# TMR2017.net
KiCad netlist of a schematic drawn in EAGLE
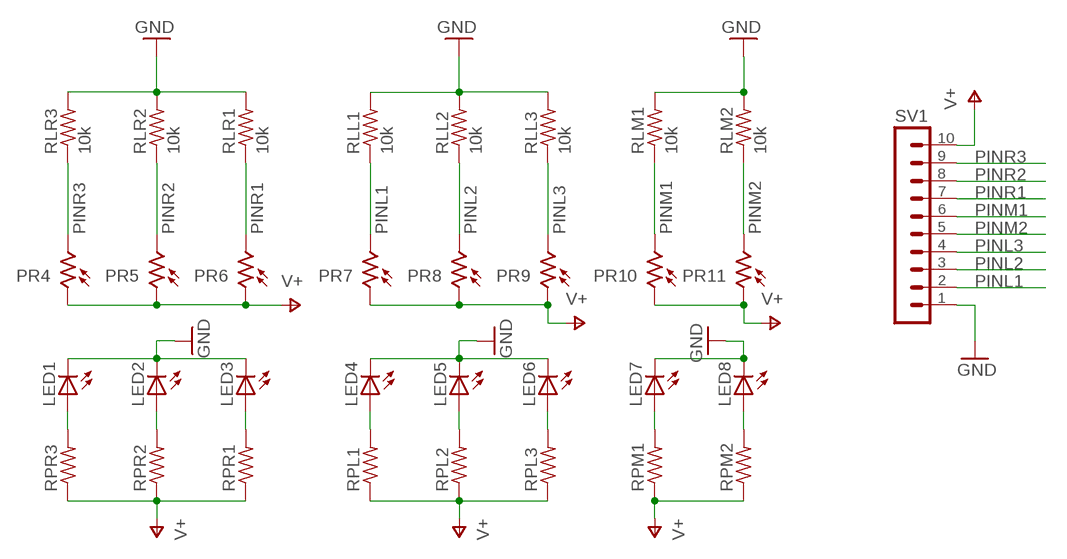
[diagram p0: schematic, sheet 1]

(export (version "E")
  (design (tool "Eeschema 10.0.6"))
  (components
    (comp (ref "LED1")
      (value "TLLR4400")
      (footprint "eagle-import:LED3MM")
      (fields (field (name "MF") "VISHAY SEMICONDUCTOR"))
      (libsource (lib "eagle-import") (part "TLLR4400"))
    )
    (comp (ref "LED2")
      (value "TLLR4400")
      (footprint "eagle-import:LED3MM")
      (fields (field (name "MF") "VISHAY SEMICONDUCTOR"))
      (libsource (lib "eagle-import") (part "TLLR4400"))
    )
    (comp (ref "LED3")
      (value "TLLR4400")
      (footprint "eagle-import:LED3MM")
      (fields (field (name "MF") "VISHAY SEMICONDUCTOR"))
      (libsource (lib "eagle-import") (part "TLLR4400"))
    )
    (comp (ref "LED4")
      (value "TLLR4400")
      (footprint "eagle-import:LED3MM")
      (fields (field (name "MF") "VISHAY SEMICONDUCTOR"))
      (libsource (lib "eagle-import") (part "TLLR4400"))
    )
    (comp (ref "LED5")
      (value "TLLR4400")
      (footprint "eagle-import:LED3MM")
      (fields (field (name "MF") "VISHAY SEMICONDUCTOR"))
      (libsource (lib "eagle-import") (part "TLLR4400"))
    )
    (comp (ref "LED6")
      (value "TLLR4400")
      (footprint "eagle-import:LED3MM")
      (fields (field (name "MF") "VISHAY SEMICONDUCTOR"))
      (libsource (lib "eagle-import") (part "TLLR4400"))
    )
    (comp (ref "LED7")
      (value "TLLR4400")
      (footprint "eagle-import:LED3MM")
      (fields (field (name "MF") "VISHAY SEMICONDUCTOR"))
      (libsource (lib "eagle-import") (part "TLLR4400"))
    )
    (comp (ref "LED8")
      (value "TLLR4400")
      (footprint "eagle-import:LED3MM")
      (fields (field (name "MF") "VISHAY SEMICONDUCTOR"))
      (libsource (lib "eagle-import") (part "TLLR4400"))
    )
    (comp (ref "PR4")
      (value "VT80N1")
      (footprint "eagle-import:VT800")
      (libsource (lib "eagle-import") (part "VT80N1"))
    )
    (comp (ref "PR5")
      (value "VT80N1")
      (footprint "eagle-import:VT800")
      (libsource (lib "eagle-import") (part "VT80N1"))
    )
    (comp (ref "PR6")
      (value "VT80N1")
      (footprint "eagle-import:VT800")
      (libsource (lib "eagle-import") (part "VT80N1"))
    )
    (comp (ref "PR7")
      (value "VT80N1")
      (footprint "eagle-import:VT800")
      (libsource (lib "eagle-import") (part "VT80N1"))
    )
    (comp (ref "PR8")
      (value "VT80N1")
      (footprint "eagle-import:VT800")
      (libsource (lib "eagle-import") (part "VT80N1"))
    )
    (comp (ref "PR9")
      (value "VT80N1")
      (footprint "eagle-import:VT800")
      (libsource (lib "eagle-import") (part "VT80N1"))
    )
    (comp (ref "PR10")
      (value "VT80N1")
      (footprint "eagle-import:VT800")
      (libsource (lib "eagle-import") (part "VT80N1"))
    )
    (comp (ref "PR11")
      (value "VT80N1")
      (footprint "eagle-import:VT800")
      (libsource (lib "eagle-import") (part "VT80N1"))
    )
    (comp (ref "RLL1")
      (value "10k")
      (footprint "eagle-import:0207_10")
      (libsource (lib "eagle-import") (part "R-US_0207/10"))
    )
    (comp (ref "RLL2")
      (value "10k")
      (footprint "eagle-import:0207_10")
      (libsource (lib "eagle-import") (part "R-US_0207/10"))
    )
    (comp (ref "RLL3")
      (value "10k")
      (footprint "eagle-import:0207_10")
      (libsource (lib "eagle-import") (part "R-US_0207/10"))
    )
    (comp (ref "RLM1")
      (value "10k")
      (footprint "eagle-import:0207_10")
      (libsource (lib "eagle-import") (part "R-US_0207/10"))
    )
    (comp (ref "RLM2")
      (value "10k")
      (footprint "eagle-import:0207_10")
      (libsource (lib "eagle-import") (part "R-US_0207/10"))
    )
    (comp (ref "RLR1")
      (value "10k")
      (footprint "eagle-import:0207_10")
      (libsource (lib "eagle-import") (part "R-US_0207/10"))
    )
    (comp (ref "RLR2")
      (value "10k")
      (footprint "eagle-import:0207_10")
      (libsource (lib "eagle-import") (part "R-US_0207/10"))
    )
    (comp (ref "RLR3")
      (value "10k")
      (footprint "eagle-import:0207_10")
      (libsource (lib "eagle-import") (part "R-US_0207/10"))
    )
    (comp (ref "RPL1")
      (value "R-US_0207/10")
      (footprint "eagle-import:0207_10")
      (libsource (lib "eagle-import") (part "R-US_0207/10"))
    )
    (comp (ref "RPL2")
      (value "R-US_0207/10")
      (footprint "eagle-import:0207_10")
      (libsource (lib "eagle-import") (part "R-US_0207/10"))
    )
    (comp (ref "RPL3")
      (value "R-US_0207/10")
      (footprint "eagle-import:0207_10")
      (libsource (lib "eagle-import") (part "R-US_0207/10"))
    )
    (comp (ref "RPM1")
      (value "R-US_0207/10")
      (footprint "eagle-import:0207_10")
      (libsource (lib "eagle-import") (part "R-US_0207/10"))
    )
    (comp (ref "RPM2")
      (value "R-US_0207/10")
      (footprint "eagle-import:0207_10")
      (libsource (lib "eagle-import") (part "R-US_0207/10"))
    )
    (comp (ref "RPR1")
      (value "R-US_0207/10")
      (footprint "eagle-import:0207_10")
      (libsource (lib "eagle-import") (part "R-US_0207/10"))
    )
    (comp (ref "RPR2")
      (value "R-US_0207/10")
      (footprint "eagle-import:0207_10")
      (libsource (lib "eagle-import") (part "R-US_0207/10"))
    )
    (comp (ref "RPR3")
      (value "R-US_0207/10")
      (footprint "eagle-import:0207_10")
      (libsource (lib "eagle-import") (part "R-US_0207/10"))
    )
    (comp (ref "SV1")
      (value "MA10-1")
      (footprint "eagle-import:MA10-1")
      (libsource (lib "eagle-import") (part "MA10-1"))
    )
  )
  (nets
    (net (code "1") (name "/PINL1") (class "Default")
      (node (ref "PR7") (pin "2") (pinfunction "2_2") (pintype "passive"))
      (node (ref "RLL1") (pin "1") (pinfunction "1_1") (pintype "passive"))
      (node (ref "SV1") (pin "2") (pinfunction "2_2") (pintype "passive"))
    )
    (net (code "2") (name "/PINL2") (class "Default")
      (node (ref "PR8") (pin "2") (pinfunction "2_2") (pintype "passive"))
      (node (ref "RLL2") (pin "1") (pinfunction "1_1") (pintype "passive"))
      (node (ref "SV1") (pin "3") (pinfunction "3_3") (pintype "passive"))
    )
    (net (code "3") (name "/PINL3") (class "Default")
      (node (ref "PR9") (pin "2") (pinfunction "2_2") (pintype "passive"))
      (node (ref "RLL3") (pin "1") (pinfunction "1_1") (pintype "passive"))
      (node (ref "SV1") (pin "4") (pinfunction "4_4") (pintype "passive"))
    )
    (net (code "4") (name "/PINM1") (class "Default")
      (node (ref "PR10") (pin "2") (pinfunction "2_2") (pintype "passive"))
      (node (ref "RLM1") (pin "1") (pinfunction "1_1") (pintype "passive"))
      (node (ref "SV1") (pin "6") (pinfunction "6_6") (pintype "passive"))
    )
    (net (code "5") (name "/PINM2") (class "Default")
      (node (ref "PR11") (pin "2") (pinfunction "2_2") (pintype "passive"))
      (node (ref "RLM2") (pin "1") (pinfunction "1_1") (pintype "passive"))
      (node (ref "SV1") (pin "5") (pinfunction "5_5") (pintype "passive"))
    )
    (net (code "6") (name "/PINR1") (class "Default")
      (node (ref "PR6") (pin "2") (pinfunction "2_2") (pintype "passive"))
      (node (ref "RLR1") (pin "1") (pinfunction "1_1") (pintype "passive"))
      (node (ref "SV1") (pin "7") (pinfunction "7_7") (pintype "passive"))
    )
    (net (code "7") (name "/PINR2") (class "Default")
      (node (ref "PR5") (pin "2") (pinfunction "2_2") (pintype "passive"))
      (node (ref "RLR2") (pin "1") (pinfunction "1_1") (pintype "passive"))
      (node (ref "SV1") (pin "8") (pinfunction "8_8") (pintype "passive"))
    )
    (net (code "8") (name "/PINR3") (class "Default")
      (node (ref "PR4") (pin "2") (pinfunction "2_2") (pintype "passive"))
      (node (ref "RLR3") (pin "1") (pinfunction "1_1") (pintype "passive"))
      (node (ref "SV1") (pin "9") (pinfunction "9_9") (pintype "passive"))
    )
    (net (code "9") (name "GND") (class "Default")
      (node (ref "LED1") (pin "K") (pinfunction "C_K") (pintype "passive"))
      (node (ref "LED2") (pin "K") (pinfunction "C_K") (pintype "passive"))
      (node (ref "LED3") (pin "K") (pinfunction "C_K") (pintype "passive"))
      (node (ref "LED4") (pin "K") (pinfunction "C_K") (pintype "passive"))
      (node (ref "LED5") (pin "K") (pinfunction "C_K") (pintype "passive"))
      (node (ref "LED6") (pin "K") (pinfunction "C_K") (pintype "passive"))
      (node (ref "LED7") (pin "K") (pinfunction "C_K") (pintype "passive"))
      (node (ref "LED8") (pin "K") (pinfunction "C_K") (pintype "passive"))
      (node (ref "RLL1") (pin "2") (pinfunction "2_2") (pintype "passive"))
      (node (ref "RLL2") (pin "2") (pinfunction "2_2") (pintype "passive"))
      (node (ref "RLL3") (pin "2") (pinfunction "2_2") (pintype "passive"))
      (node (ref "RLM1") (pin "2") (pinfunction "2_2") (pintype "passive"))
      (node (ref "RLM2") (pin "2") (pinfunction "2_2") (pintype "passive"))
      (node (ref "RLR1") (pin "2") (pinfunction "2_2") (pintype "passive"))
      (node (ref "RLR2") (pin "2") (pinfunction "2_2") (pintype "passive"))
      (node (ref "RLR3") (pin "2") (pinfunction "2_2") (pintype "passive"))
      (node (ref "SV1") (pin "1") (pinfunction "1_1") (pintype "passive"))
    )
    (net (code "10") (name "Net-(LED1-PadA)") (class "Default")
      (node (ref "LED1") (pin "A") (pinfunction "A_A") (pintype "passive"))
      (node (ref "RPR3") (pin "2") (pinfunction "2_2") (pintype "passive"))
    )
    (net (code "11") (name "Net-(LED2-PadA)") (class "Default")
      (node (ref "LED2") (pin "A") (pinfunction "A_A") (pintype "passive"))
      (node (ref "RPR2") (pin "2") (pinfunction "2_2") (pintype "passive"))
    )
    (net (code "12") (name "Net-(LED3-PadA)") (class "Default")
      (node (ref "LED3") (pin "A") (pinfunction "A_A") (pintype "passive"))
      (node (ref "RPR1") (pin "2") (pinfunction "2_2") (pintype "passive"))
    )
    (net (code "13") (name "Net-(LED4-PadA)") (class "Default")
      (node (ref "LED4") (pin "A") (pinfunction "A_A") (pintype "passive"))
      (node (ref "RPL1") (pin "2") (pinfunction "2_2") (pintype "passive"))
    )
    (net (code "14") (name "Net-(LED5-PadA)") (class "Default")
      (node (ref "LED5") (pin "A") (pinfunction "A_A") (pintype "passive"))
      (node (ref "RPL2") (pin "2") (pinfunction "2_2") (pintype "passive"))
    )
    (net (code "15") (name "Net-(LED6-PadA)") (class "Default")
      (node (ref "LED6") (pin "A") (pinfunction "A_A") (pintype "passive"))
      (node (ref "RPL3") (pin "2") (pinfunction "2_2") (pintype "passive"))
    )
    (net (code "16") (name "Net-(LED7-PadA)") (class "Default")
      (node (ref "LED7") (pin "A") (pinfunction "A_A") (pintype "passive"))
      (node (ref "RPM1") (pin "2") (pinfunction "2_2") (pintype "passive"))
    )
    (net (code "17") (name "Net-(LED8-PadA)") (class "Default")
      (node (ref "LED8") (pin "A") (pinfunction "A_A") (pintype "passive"))
      (node (ref "RPM2") (pin "2") (pinfunction "2_2") (pintype "passive"))
    )
    (net (code "18") (name "V+") (class "Default")
      (node (ref "PR10") (pin "1") (pinfunction "1_1") (pintype "passive"))
      (node (ref "PR11") (pin "1") (pinfunction "1_1") (pintype "passive"))
      (node (ref "PR4") (pin "1") (pinfunction "1_1") (pintype "passive"))
      (node (ref "PR5") (pin "1") (pinfunction "1_1") (pintype "passive"))
      (node (ref "PR6") (pin "1") (pinfunction "1_1") (pintype "passive"))
      (node (ref "PR7") (pin "1") (pinfunction "1_1") (pintype "passive"))
      (node (ref "PR8") (pin "1") (pinfunction "1_1") (pintype "passive"))
      (node (ref "PR9") (pin "1") (pinfunction "1_1") (pintype "passive"))
      (node (ref "RPL1") (pin "1") (pinfunction "1_1") (pintype "passive"))
      (node (ref "RPL2") (pin "1") (pinfunction "1_1") (pintype "passive"))
      (node (ref "RPL3") (pin "1") (pinfunction "1_1") (pintype "passive"))
      (node (ref "RPM1") (pin "1") (pinfunction "1_1") (pintype "passive"))
      (node (ref "RPM2") (pin "1") (pinfunction "1_1") (pintype "passive"))
      (node (ref "RPR1") (pin "1") (pinfunction "1_1") (pintype "passive"))
      (node (ref "RPR2") (pin "1") (pinfunction "1_1") (pintype "passive"))
      (node (ref "RPR3") (pin "1") (pinfunction "1_1") (pintype "passive"))
      (node (ref "SV1") (pin "10") (pinfunction "10_10") (pintype "passive"))
    )
  )
)
